# MASTER_GPIO.net
KiCad netlist of a schematic drawn in Altium Designer
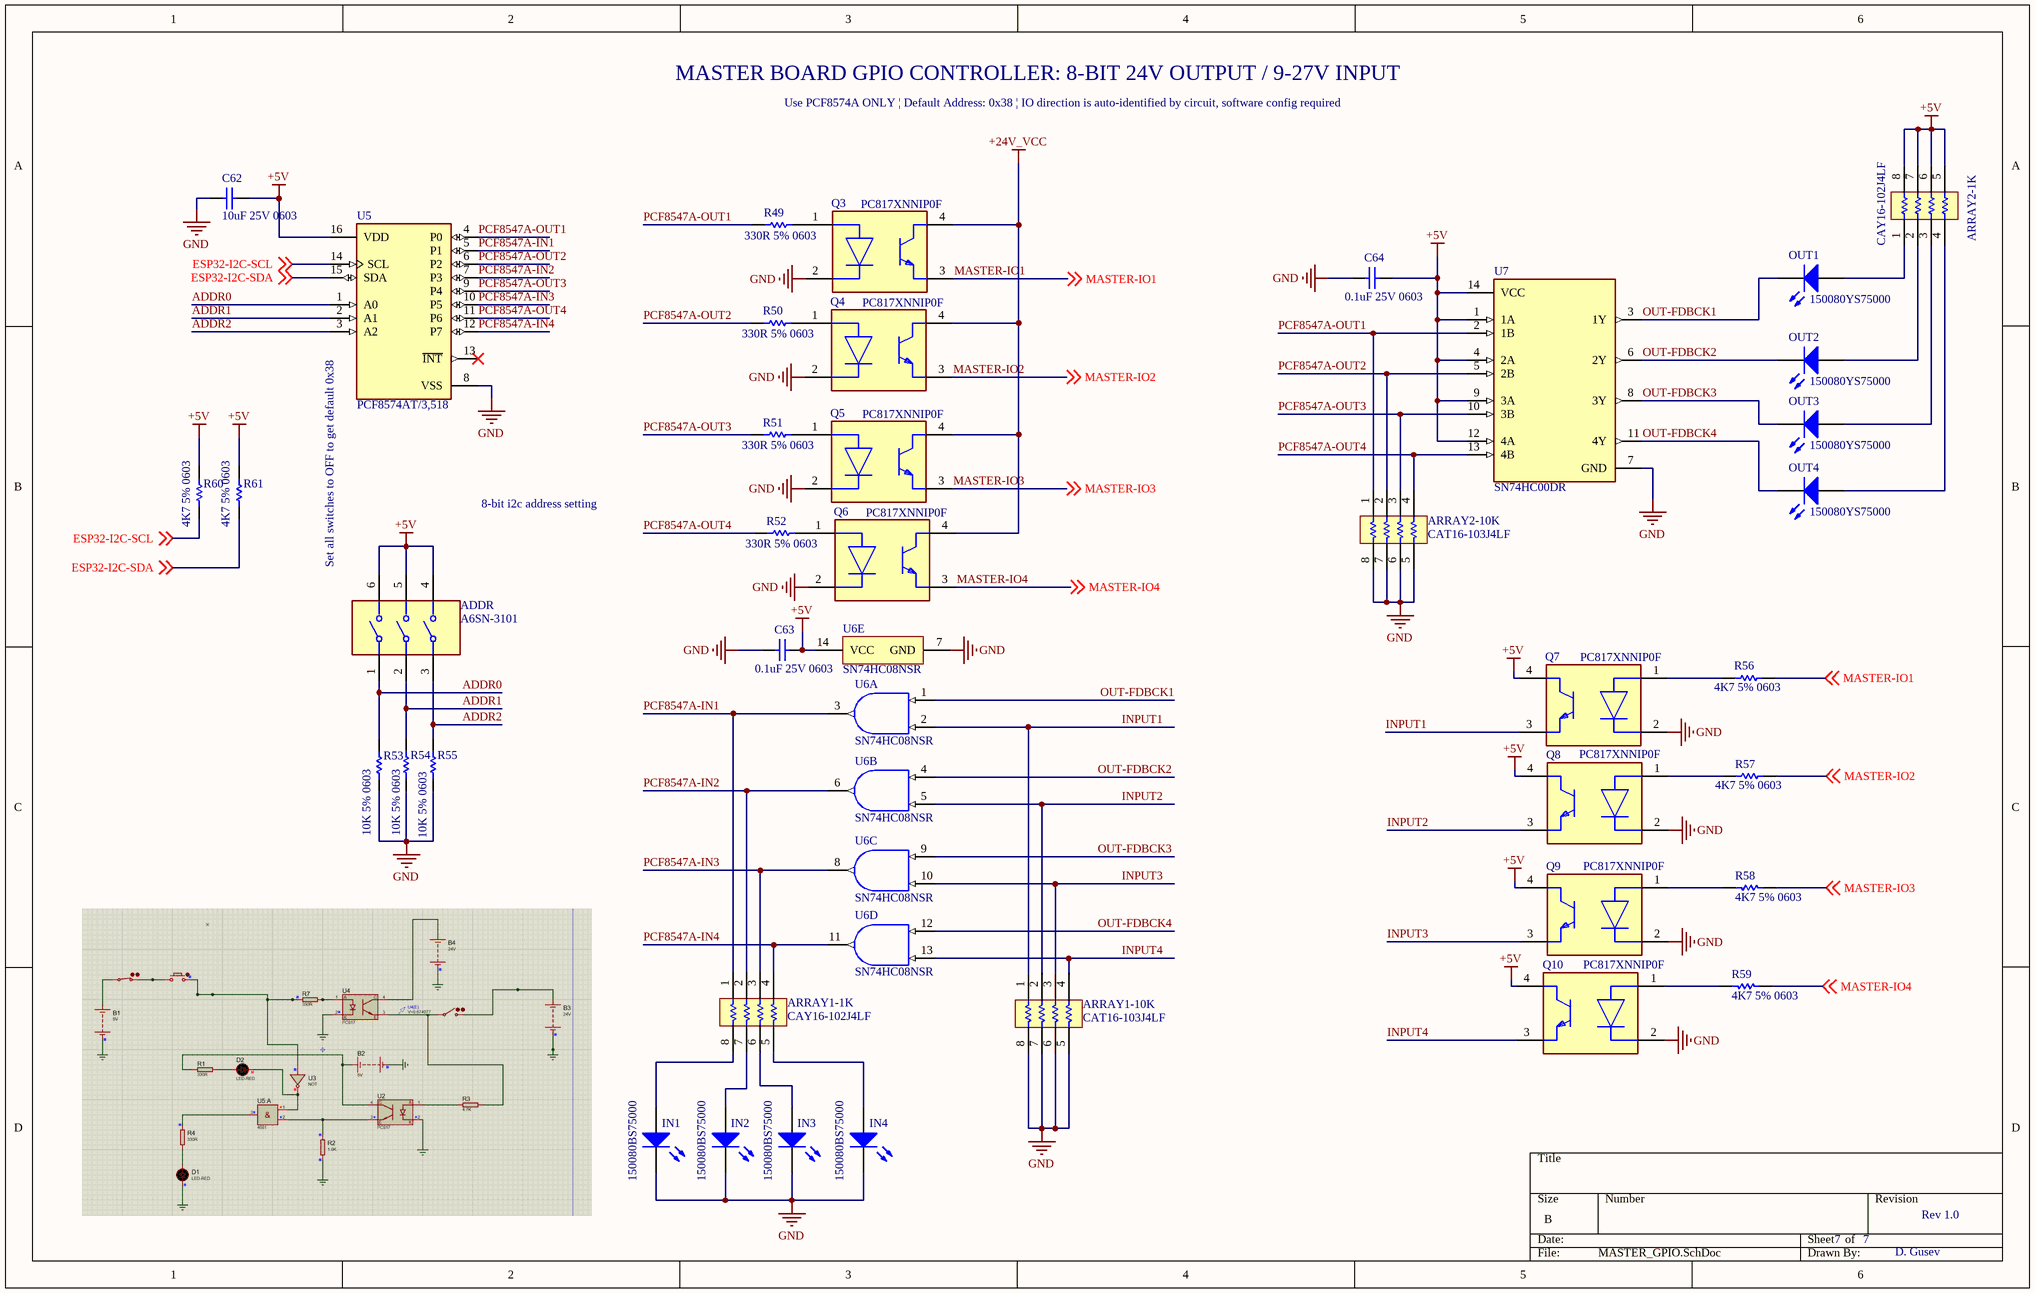
[diagram p0: MASTER_GPIO.SchDoc]

(export (version "E")
  (design (tool "Eeschema 10.0.6"))
  (components
    (comp (ref "ADDR")
      (value "A6SN-3101")
      (footprint "FP-A6SN-3101-MFG")
      (description "SWITCH SLIDE DIP SPST 25MA 24V")
      (fields
        (field (name "MANUFACTURER") "Omron Electronics Inc-EMC Div")
        (field (name "OCTOPART") "https://octopart.com/a6sn-3101-omron-55396000")
      )
      (libsource (lib "Altium Content Vault") (part "c5ed29025a0a80be921a75429a93ff4"))
    )
    (comp (ref "ARRAY1-1K")
      (value "CAY16-102J4LF")
      (footprint "BOUR-CAY16-J4_V")
      (description "Chip Resistor Array, 1 KOhm, +/- 5%, 62.5 mW, -55 to 125 degC, 8-Pin SMD, RoHS, Tape and Reel")
      (fields (field (name "TOLERANCE") "1%"))
      (libsource (lib "Altium Content Vault") (part "RES-P-8"))
    )
    (comp (ref "ARRAY1-10K")
      (value "CAT16-103J4LF")
      (footprint "BOUR-CAT16-103J4LF_L")
      (fields (field (name "MANUFACTURER") "Bourns") (field (name "TOLERANCE") "±5%"))
      (libsource (lib "Altium Content Vault") (part "RES-P-8"))
    )
    (comp (ref "ARRAY2-1K")
      (value "CAY16-102J4LF")
      (footprint "BOUR-CAY16-J4_V")
      (description "Chip Resistor Array, 1 KOhm, +/- 5%, 62.5 mW, -55 to 125 degC, 8-Pin SMD, RoHS, Tape and Reel")
      (fields (field (name "TOLERANCE") "1%"))
      (libsource (lib "") (part "RES-P-8_1"))
    )
    (comp (ref "ARRAY2-10K")
      (value "CAT16-103J4LF")
      (footprint "BOUR-CAT16-103J4LF_L")
      (fields (field (name "MANUFACTURER") "Bourns") (field (name "TOLERANCE") "±5%"))
      (libsource (lib "Altium Content Vault") (part "RES-P-8"))
    )
    (comp (ref "C62")
      (value "10uF 25V 0603")
      (footprint "CAPC1608X100X20VL10T10")
      (description "Chip Capacitor, 10 uF, +/- 20%, 25 V, -55 to 85 degC, 0603 (1608 Metric), RoHS, Tape and Reel")
      (fields (field (name "MANUFACTURER") "TDK") (field (name "TOLERANCE") "±20%"))
      (libsource (lib "Altium Content Vault") (part "CAP-NP-2"))
    )
    (comp (ref "C63")
      (value "0.1uF 25V 0603")
      (footprint "CAPC1608X90X35LL10T15")
      (fields (field (name "PART NUMBER") "GRM188R71E104KA01D") (field (name "MANUFACTURER") "Murata"))
      (libsource (lib "Altium Content Vault") (part "CAP"))
    )
    (comp (ref "C64")
      (value "0.1uF 25V 0603")
      (footprint "CAPC1608X90X35LL10T15")
      (fields (field (name "PART NUMBER") "GRM188R71E104KA01D") (field (name "MANUFACTURER") "Murata"))
      (libsource (lib "Altium Content Vault") (part "CAP"))
    )
    (comp (ref "IN1")
      (value "150080BS75000")
      (footprint "0805_A")
      (description "SMD mono-color Chip LED, WL-SMCW, Blue")
      (fields (field (name "MANUFACTURER") "Wuerth Elektronik"))
      (libsource (lib "Altium Content Vault") (part "WE-LED_K1A2-2"))
    )
    (comp (ref "IN2")
      (value "150080BS75000")
      (footprint "0805_A")
      (description "SMD mono-color Chip LED, WL-SMCW, Blue")
      (fields (field (name "MANUFACTURER") "Wuerth Elektronik"))
      (libsource (lib "Altium Content Vault") (part "WE-LED_K1A2-2"))
    )
    (comp (ref "IN3")
      (value "150080BS75000")
      (footprint "0805_A")
      (description "SMD mono-color Chip LED, WL-SMCW, Blue")
      (fields (field (name "MANUFACTURER") "Wuerth Elektronik"))
      (libsource (lib "Altium Content Vault") (part "WE-LED_K1A2-2"))
    )
    (comp (ref "IN4")
      (value "150080BS75000")
      (footprint "0805_A")
      (description "SMD mono-color Chip LED, WL-SMCW, Blue")
      (fields (field (name "MANUFACTURER") "Wuerth Elektronik"))
      (libsource (lib "Altium Content Vault") (part "WE-LED_K1A2-2"))
    )
    (comp (ref "OUT1")
      (value "150080YS75000")
      (footprint "0805_A")
      (description "SMD mono-color Chip LED, WL-SMCW, Yellow")
      (fields (field (name "MANUFACTURER") "Wuerth Elektronik"))
      (libsource (lib "Altium Content Vault") (part "WE-LED_K1A2-2"))
    )
    (comp (ref "OUT2")
      (value "150080YS75000")
      (footprint "0805_A")
      (description "SMD mono-color Chip LED, WL-SMCW, Yellow")
      (fields (field (name "MANUFACTURER") "Wuerth Elektronik"))
      (libsource (lib "Altium Content Vault") (part "WE-LED_K1A2-2"))
    )
    (comp (ref "OUT3")
      (value "150080YS75000")
      (footprint "0805_A")
      (description "SMD mono-color Chip LED, WL-SMCW, Yellow")
      (fields (field (name "MANUFACTURER") "Wuerth Elektronik"))
      (libsource (lib "Altium Content Vault") (part "WE-LED_K1A2-2"))
    )
    (comp (ref "OUT4")
      (value "150080YS75000")
      (footprint "0805_A")
      (description "SMD mono-color Chip LED, WL-SMCW, Yellow")
      (fields (field (name "MANUFACTURER") "Wuerth Elektronik"))
      (libsource (lib "Altium Content Vault") (part "WE-LED_K1A2-2"))
    )
    (comp (ref "Q3")
      (value "PC817XNNIP0F")
      (footprint "FP-PC817XNNIP0F-MFG")
      (description "OPTOISOLATOR 5KV TRANS 4SMD")
      (libsource (lib "") (part "6470904bf6395c62928ee73e60120b8_1"))
    )
    (comp (ref "Q4")
      (value "PC817XNNIP0F")
      (footprint "FP-PC817XNNIP0F-MFG")
      (description "OPTOISOLATOR 5KV TRANS 4SMD")
      (libsource (lib "") (part "6470904bf6395c62928ee73e60120b8_1"))
    )
    (comp (ref "Q5")
      (value "PC817XNNIP0F")
      (footprint "FP-PC817XNNIP0F-MFG")
      (description "OPTOISOLATOR 5KV TRANS 4SMD")
      (libsource (lib "") (part "6470904bf6395c62928ee73e60120b8_1"))
    )
    (comp (ref "Q6")
      (value "PC817XNNIP0F")
      (footprint "FP-PC817XNNIP0F-MFG")
      (description "OPTOISOLATOR 5KV TRANS 4SMD")
      (libsource (lib "") (part "6470904bf6395c62928ee73e60120b8_1"))
    )
    (comp (ref "Q7")
      (value "PC817XNNIP0F")
      (footprint "FP-PC817XNNIP0F-MFG")
      (description "OPTOISOLATOR 5KV TRANS 4SMD")
      (libsource (lib "Altium Content Vault") (part "6470904bf6395c62928ee73e60120b8"))
    )
    (comp (ref "Q8")
      (value "PC817XNNIP0F")
      (footprint "FP-PC817XNNIP0F-MFG")
      (description "OPTOISOLATOR 5KV TRANS 4SMD")
      (libsource (lib "Altium Content Vault") (part "6470904bf6395c62928ee73e60120b8"))
    )
    (comp (ref "Q9")
      (value "PC817XNNIP0F")
      (footprint "FP-PC817XNNIP0F-MFG")
      (description "OPTOISOLATOR 5KV TRANS 4SMD")
      (libsource (lib "Altium Content Vault") (part "6470904bf6395c62928ee73e60120b8"))
    )
    (comp (ref "Q10")
      (value "PC817XNNIP0F")
      (footprint "FP-PC817XNNIP0F-MFG")
      (description "OPTOISOLATOR 5KV TRANS 4SMD")
      (libsource (lib "Altium Content Vault") (part "6470904bf6395c62928ee73e60120b8"))
    )
    (comp (ref "R49")
      (value "330R 5% 0603")
      (footprint "RESC1608X55X25NL10T15")
      (description "Chip Resistor, 330 Ohm, +/- 1%, 0.1 W, -55 to 155 degC, 0603 (1608 Metric), RoHS, Tape and Reel")
      (fields (field (name "TOLERANCE") "10%"))
      (libsource (lib "Altium Content Vault") (part "RES-2"))
    )
    (comp (ref "R50")
      (value "330R 5% 0603")
      (footprint "RESC1608X55X25NL10T15")
      (description "Chip Resistor, 330 Ohm, +/- 1%, 0.1 W, -55 to 155 degC, 0603 (1608 Metric), RoHS, Tape and Reel")
      (fields (field (name "TOLERANCE") "10%"))
      (libsource (lib "Altium Content Vault") (part "RES-2"))
    )
    (comp (ref "R51")
      (value "330R 5% 0603")
      (footprint "RESC1608X55X25NL10T15")
      (description "Chip Resistor, 330 Ohm, +/- 1%, 0.1 W, -55 to 155 degC, 0603 (1608 Metric), RoHS, Tape and Reel")
      (fields (field (name "TOLERANCE") "10%"))
      (libsource (lib "Altium Content Vault") (part "RES-2"))
    )
    (comp (ref "R52")
      (value "330R 5% 0603")
      (footprint "RESC1608X55X25NL10T15")
      (description "Chip Resistor, 330 Ohm, +/- 1%, 0.1 W, -55 to 155 degC, 0603 (1608 Metric), RoHS, Tape and Reel")
      (fields (field (name "TOLERANCE") "10%"))
      (libsource (lib "Altium Content Vault") (part "RES-2"))
    )
    (comp (ref "R53")
      (value "10K 5% 0603")
      (footprint "RESC1608X55X25ML10T15")
      (description "Chip Resistor, 10 KOhm, +/- 1%, 01 W, -55 to 155 degC, 0603 (1608 Metric), RoHS, Tape and Reel")
      (fields (field (name "MANUFACTURER") "Yageo") (field (name "TOLERANCE") "1%"))
      (libsource (lib "Altium Content Vault") (part "RES-2"))
    )
    (comp (ref "R54")
      (value "10K 5% 0603")
      (footprint "RESC1608X55X25ML10T15")
      (description "Chip Resistor, 10 KOhm, +/- 1%, 01 W, -55 to 155 degC, 0603 (1608 Metric), RoHS, Tape and Reel")
      (fields (field (name "MANUFACTURER") "Yageo") (field (name "TOLERANCE") "1%"))
      (libsource (lib "Altium Content Vault") (part "RES-2"))
    )
    (comp (ref "R55")
      (value "10K 5% 0603")
      (footprint "RESC1608X55X25ML10T15")
      (description "Chip Resistor, 10 KOhm, +/- 1%, 01 W, -55 to 155 degC, 0603 (1608 Metric), RoHS, Tape and Reel")
      (fields (field (name "MANUFACTURER") "Yageo") (field (name "TOLERANCE") "1%"))
      (libsource (lib "Altium Content Vault") (part "RES-2"))
    )
    (comp (ref "R56")
      (value "4K7 5% 0603")
      (footprint "RESC1608X55X25LL10T15")
      (description "Chip Resistor, 4.7 KOhm, +/- 1%, 0.1 W, -55 to 155 degC, 0603 (1608 Metric), RoHS, Tape and Reel")
      (fields (field (name "MANUFACTURER") "Yageo") (field (name "TOLERANCE") "1%"))
      (libsource (lib "Altium Content Vault") (part "RES-2"))
    )
    (comp (ref "R57")
      (value "4K7 5% 0603")
      (footprint "RESC1608X55X25LL10T15")
      (description "Chip Resistor, 4.7 KOhm, +/- 1%, 0.1 W, -55 to 155 degC, 0603 (1608 Metric), RoHS, Tape and Reel")
      (fields (field (name "MANUFACTURER") "Yageo") (field (name "TOLERANCE") "1%"))
      (libsource (lib "Altium Content Vault") (part "RES-2"))
    )
    (comp (ref "R58")
      (value "4K7 5% 0603")
      (footprint "RESC1608X55X25LL10T15")
      (description "Chip Resistor, 4.7 KOhm, +/- 1%, 0.1 W, -55 to 155 degC, 0603 (1608 Metric), RoHS, Tape and Reel")
      (fields (field (name "MANUFACTURER") "Yageo") (field (name "TOLERANCE") "1%"))
      (libsource (lib "Altium Content Vault") (part "RES-2"))
    )
    (comp (ref "R59")
      (value "4K7 5% 0603")
      (footprint "RESC1608X55X25LL10T15")
      (description "Chip Resistor, 4.7 KOhm, +/- 1%, 0.1 W, -55 to 155 degC, 0603 (1608 Metric), RoHS, Tape and Reel")
      (fields (field (name "MANUFACTURER") "Yageo") (field (name "TOLERANCE") "1%"))
      (libsource (lib "Altium Content Vault") (part "RES-2"))
    )
    (comp (ref "R60")
      (value "4K7 5% 0603")
      (footprint "RESC1608X55X25LL10T15")
      (description "Chip Resistor, 4.7 KOhm, +/- 1%, 0.1 W, -55 to 155 degC, 0603 (1608 Metric), RoHS, Tape and Reel")
      (fields (field (name "MANUFACTURER") "Yageo") (field (name "TOLERANCE") "1%"))
      (libsource (lib "Altium Content Vault") (part "RES-2"))
    )
    (comp (ref "R61")
      (value "4K7 5% 0603")
      (footprint "RESC1608X55X25LL10T15")
      (description "Chip Resistor, 4.7 KOhm, +/- 1%, 0.1 W, -55 to 155 degC, 0603 (1608 Metric), RoHS, Tape and Reel")
      (fields (field (name "MANUFACTURER") "Yageo") (field (name "TOLERANCE") "1%"))
      (libsource (lib "Altium Content Vault") (part "RES-2"))
    )
    (comp (ref "U5")
      (value "PCF8574AT/3,518")
      (footprint "FP-SOT162-1-MFG")
      (description "IC I/O EXPANDER I2C 8B 16SOIC")
      (fields
        (field (name "MANUFACTURER") "NXP Semiconductors")
        (field (name "OCTOPART") "https://octopart.com/pcf8574at%2F3%2C518-nxp+semiconductors-11541925")
      )
      (libsource (lib "Altium Content Vault") (part "f7fde53ce59de981fb0b266a4e103eb"))
    )
    (comp (ref "U6")
      (value "SN74HC08NSR")
      (footprint "NS0014A_M")
      (description "Quadruple 2-Input Positive-AND Gates, NS0014A, LARGE T&R")
      (fields
        (field (name "GENERIC PART NUMBER") "SN74HC08")
        (field (name "MANUFACTURER") "Texas Instruments")
      )
      (libsource (lib "") (part "TI-AND-4-2IN-14_1"))
    )
    (comp (ref "U7")
      (value "SN74HC00DR")
      (footprint "FP-D0014A-MFG")
      (description "IC GATE NAND 4CH 2-INP 14SOIC")
      (libsource (lib "Altium Content Vault") (part "2c7ba7b3eb294338d27c07afa77b609"))
    )
  )
  (nets
    (net (code "1") (name "+5V") (class "Default")
      (node (ref "ADDR") (pin "4") (pinfunction "4_4") (pintype "passive"))
      (node (ref "ADDR") (pin "5") (pinfunction "5_5") (pintype "passive"))
      (node (ref "ADDR") (pin "6") (pinfunction "6_6") (pintype "passive"))
      (node (ref "ARRAY2-1K") (pin "5") (pinfunction "5_5") (pintype "passive"))
      (node (ref "ARRAY2-1K") (pin "6") (pinfunction "6_6") (pintype "passive"))
      (node (ref "ARRAY2-1K") (pin "7") (pinfunction "7_7") (pintype "passive"))
      (node (ref "ARRAY2-1K") (pin "8") (pinfunction "8_8") (pintype "passive"))
      (node (ref "C62") (pin "1") (pinfunction "1_1") (pintype "passive"))
      (node (ref "C63") (pin "1") (pinfunction "1_1") (pintype "passive"))
      (node (ref "C64") (pin "1") (pinfunction "1_1") (pintype "passive"))
      (node (ref "Q10") (pin "4") (pinfunction "C_4") (pintype "passive"))
      (node (ref "Q7") (pin "4") (pinfunction "C_4") (pintype "passive"))
      (node (ref "Q8") (pin "4") (pinfunction "C_4") (pintype "passive"))
      (node (ref "Q9") (pin "4") (pinfunction "C_4") (pintype "passive"))
      (node (ref "R60") (pin "2") (pinfunction "2_2") (pintype "passive"))
      (node (ref "R61") (pin "2") (pinfunction "2_2") (pintype "passive"))
      (node (ref "U5") (pin "16") (pinfunction "VDD_16") (pintype "power_in"))
      (node (ref "U6") (pin "14") (pinfunction "VCC_14") (pintype "power_in"))
      (node (ref "U7") (pin "1") (pinfunction "1A_1") (pintype "input"))
      (node (ref "U7") (pin "12") (pinfunction "4A_12") (pintype "input"))
      (node (ref "U7") (pin "14") (pinfunction "VCC_14") (pintype "power_in"))
      (node (ref "U7") (pin "4") (pinfunction "2A_4") (pintype "input"))
      (node (ref "U7") (pin "9") (pinfunction "3A_9") (pintype "input"))
    )
    (net (code "2") (name "+24V_VCC") (class "Default")
      (node (ref "Q3") (pin "4") (pinfunction "C_4") (pintype "passive"))
      (node (ref "Q4") (pin "4") (pinfunction "C_4") (pintype "passive"))
      (node (ref "Q5") (pin "4") (pinfunction "C_4") (pintype "passive"))
      (node (ref "Q6") (pin "4") (pinfunction "C_4") (pintype "passive"))
    )
    (net (code "3") (name "/ADDR0") (class "Default")
      (node (ref "ADDR") (pin "1") (pinfunction "1_1") (pintype "passive"))
      (node (ref "R53") (pin "2") (pinfunction "2_2") (pintype "passive"))
      (node (ref "U5") (pin "1") (pinfunction "A0_1") (pintype "input"))
    )
    (net (code "4") (name "/ADDR1") (class "Default")
      (node (ref "ADDR") (pin "2") (pinfunction "2_2") (pintype "passive"))
      (node (ref "R54") (pin "2") (pinfunction "2_2") (pintype "passive"))
      (node (ref "U5") (pin "2") (pinfunction "A1_2") (pintype "input"))
    )
    (net (code "5") (name "/ADDR2") (class "Default")
      (node (ref "ADDR") (pin "3") (pinfunction "3_3") (pintype "passive"))
      (node (ref "R55") (pin "2") (pinfunction "2_2") (pintype "passive"))
      (node (ref "U5") (pin "3") (pinfunction "A2_3") (pintype "input"))
    )
    (net (code "6") (name "/INPUT1") (class "Default")
      (node (ref "ARRAY1-10K") (pin "1") (pinfunction "1_1") (pintype "passive"))
      (node (ref "Q7") (pin "3") (pinfunction "E_3") (pintype "passive"))
      (node (ref "U6") (pin "2") (pinfunction "1B_2") (pintype "input"))
    )
    (net (code "7") (name "/INPUT2") (class "Default")
      (node (ref "ARRAY1-10K") (pin "2") (pinfunction "2_2") (pintype "passive"))
      (node (ref "Q8") (pin "3") (pinfunction "E_3") (pintype "passive"))
      (node (ref "U6") (pin "5") (pinfunction "2B_5") (pintype "input"))
    )
    (net (code "8") (name "/INPUT3") (class "Default")
      (node (ref "ARRAY1-10K") (pin "3") (pinfunction "3_3") (pintype "passive"))
      (node (ref "Q9") (pin "3") (pinfunction "E_3") (pintype "passive"))
      (node (ref "U6") (pin "10") (pinfunction "3B_10") (pintype "input"))
    )
    (net (code "9") (name "/INPUT4") (class "Default")
      (node (ref "ARRAY1-10K") (pin "4") (pinfunction "4_4") (pintype "passive"))
      (node (ref "Q10") (pin "3") (pinfunction "E_3") (pintype "passive"))
      (node (ref "U6") (pin "13") (pinfunction "4B_13") (pintype "input"))
    )
    (net (code "10") (name "/OUT-FDBCK1") (class "Default")
      (node (ref "OUT1") (pin "1") (pinfunction "K_1") (pintype "passive"))
      (node (ref "U6") (pin "1") (pinfunction "1A_1") (pintype "input"))
      (node (ref "U7") (pin "3") (pinfunction "1Y_3") (pintype "output"))
    )
    (net (code "11") (name "/OUT-FDBCK2") (class "Default")
      (node (ref "OUT2") (pin "1") (pinfunction "K_1") (pintype "passive"))
      (node (ref "U6") (pin "4") (pinfunction "2A_4") (pintype "input"))
      (node (ref "U7") (pin "6") (pinfunction "2Y_6") (pintype "output"))
    )
    (net (code "12") (name "/OUT-FDBCK3") (class "Default")
      (node (ref "OUT3") (pin "1") (pinfunction "K_1") (pintype "passive"))
      (node (ref "U6") (pin "9") (pinfunction "3A_9") (pintype "input"))
      (node (ref "U7") (pin "8") (pinfunction "3Y_8") (pintype "output"))
    )
    (net (code "13") (name "/OUT-FDBCK4") (class "Default")
      (node (ref "OUT4") (pin "1") (pinfunction "K_1") (pintype "passive"))
      (node (ref "U6") (pin "12") (pinfunction "4A_12") (pintype "input"))
      (node (ref "U7") (pin "11") (pinfunction "4Y_11") (pintype "output"))
    )
    (net (code "14") (name "/PCF8547A-IN1") (class "Default")
      (node (ref "ARRAY1-1K") (pin "1") (pinfunction "1_1") (pintype "passive"))
      (node (ref "U5") (pin "5") (pinfunction "P1_5") (pintype "bidirectional"))
      (node (ref "U6") (pin "3") (pinfunction "1Y_3") (pintype "output"))
    )
    (net (code "15") (name "/PCF8547A-IN2") (class "Default")
      (node (ref "ARRAY1-1K") (pin "2") (pinfunction "2_2") (pintype "passive"))
      (node (ref "U5") (pin "7") (pinfunction "P3_7") (pintype "bidirectional"))
      (node (ref "U6") (pin "6") (pinfunction "2Y_6") (pintype "output"))
    )
    (net (code "16") (name "/PCF8547A-IN3") (class "Default")
      (node (ref "ARRAY1-1K") (pin "3") (pinfunction "3_3") (pintype "passive"))
      (node (ref "U5") (pin "10") (pinfunction "P5_10") (pintype "bidirectional"))
      (node (ref "U6") (pin "8") (pinfunction "3Y_8") (pintype "output"))
    )
    (net (code "17") (name "/PCF8547A-IN4") (class "Default")
      (node (ref "ARRAY1-1K") (pin "4") (pinfunction "4_4") (pintype "passive"))
      (node (ref "U5") (pin "12") (pinfunction "P7_12") (pintype "bidirectional"))
      (node (ref "U6") (pin "11") (pinfunction "4Y_11") (pintype "output"))
    )
    (net (code "18") (name "/PCF8547A-OUT1") (class "Default")
      (node (ref "ARRAY2-10K") (pin "1") (pinfunction "1_1") (pintype "passive"))
      (node (ref "R49") (pin "1") (pinfunction "1_1") (pintype "passive"))
      (node (ref "U5") (pin "4") (pinfunction "P0_4") (pintype "bidirectional"))
      (node (ref "U7") (pin "2") (pinfunction "1B_2") (pintype "input"))
    )
    (net (code "19") (name "/PCF8547A-OUT2") (class "Default")
      (node (ref "ARRAY2-10K") (pin "2") (pinfunction "2_2") (pintype "passive"))
      (node (ref "R50") (pin "1") (pinfunction "1_1") (pintype "passive"))
      (node (ref "U5") (pin "6") (pinfunction "P2_6") (pintype "bidirectional"))
      (node (ref "U7") (pin "5") (pinfunction "2B_5") (pintype "input"))
    )
    (net (code "20") (name "/PCF8547A-OUT3") (class "Default")
      (node (ref "ARRAY2-10K") (pin "3") (pinfunction "3_3") (pintype "passive"))
      (node (ref "R51") (pin "1") (pinfunction "1_1") (pintype "passive"))
      (node (ref "U5") (pin "9") (pinfunction "P4_9") (pintype "bidirectional"))
      (node (ref "U7") (pin "10") (pinfunction "3B_10") (pintype "input"))
    )
    (net (code "21") (name "/PCF8547A-OUT4") (class "Default")
      (node (ref "ARRAY2-10K") (pin "4") (pinfunction "4_4") (pintype "passive"))
      (node (ref "R52") (pin "1") (pinfunction "1_1") (pintype "passive"))
      (node (ref "U5") (pin "11") (pinfunction "P6_11") (pintype "bidirectional"))
      (node (ref "U7") (pin "13") (pinfunction "4B_13") (pintype "input"))
    )
    (net (code "22") (name "ESP32-I2C-SCL") (class "Default")
      (node (ref "R60") (pin "1") (pinfunction "1_1") (pintype "passive"))
      (node (ref "U5") (pin "14") (pinfunction "SCL_14") (pintype "input"))
    )
    (net (code "23") (name "ESP32-I2C-SDA") (class "Default")
      (node (ref "R61") (pin "1") (pinfunction "1_1") (pintype "passive"))
      (node (ref "U5") (pin "15") (pinfunction "SDA_15") (pintype "bidirectional"))
    )
    (net (code "24") (name "GND") (class "Default")
      (node (ref "ARRAY1-10K") (pin "5") (pinfunction "5_5") (pintype "passive"))
      (node (ref "ARRAY1-10K") (pin "6") (pinfunction "6_6") (pintype "passive"))
      (node (ref "ARRAY1-10K") (pin "7") (pinfunction "7_7") (pintype "passive"))
      (node (ref "ARRAY1-10K") (pin "8") (pinfunction "8_8") (pintype "passive"))
      (node (ref "ARRAY2-10K") (pin "5") (pinfunction "5_5") (pintype "passive"))
      (node (ref "ARRAY2-10K") (pin "6") (pinfunction "6_6") (pintype "passive"))
      (node (ref "ARRAY2-10K") (pin "7") (pinfunction "7_7") (pintype "passive"))
      (node (ref "ARRAY2-10K") (pin "8") (pinfunction "8_8") (pintype "passive"))
      (node (ref "C62") (pin "2") (pinfunction "2_2") (pintype "passive"))
      (node (ref "C63") (pin "2") (pinfunction "2_2") (pintype "passive"))
      (node (ref "C64") (pin "2") (pinfunction "2_2") (pintype "passive"))
      (node (ref "IN1") (pin "1") (pinfunction "K_1") (pintype "passive"))
      (node (ref "IN2") (pin "1") (pinfunction "K_1") (pintype "passive"))
      (node (ref "IN3") (pin "1") (pinfunction "K_1") (pintype "passive"))
      (node (ref "IN4") (pin "1") (pinfunction "K_1") (pintype "passive"))
      (node (ref "Q10") (pin "2") (pinfunction "C_2") (pintype "passive"))
      (node (ref "Q3") (pin "2") (pinfunction "C_2") (pintype "passive"))
      (node (ref "Q4") (pin "2") (pinfunction "C_2") (pintype "passive"))
      (node (ref "Q5") (pin "2") (pinfunction "C_2") (pintype "passive"))
      (node (ref "Q6") (pin "2") (pinfunction "C_2") (pintype "passive"))
      (node (ref "Q7") (pin "2") (pinfunction "C_2") (pintype "passive"))
      (node (ref "Q8") (pin "2") (pinfunction "C_2") (pintype "passive"))
      (node (ref "Q9") (pin "2") (pinfunction "C_2") (pintype "passive"))
      (node (ref "R53") (pin "1") (pinfunction "1_1") (pintype "passive"))
      (node (ref "R54") (pin "1") (pinfunction "1_1") (pintype "passive"))
      (node (ref "R55") (pin "1") (pinfunction "1_1") (pintype "passive"))
      (node (ref "U5") (pin "8") (pinfunction "VSS_8") (pintype "power_in"))
      (node (ref "U6") (pin "7") (pinfunction "GND_7") (pintype "power_in"))
      (node (ref "U7") (pin "7") (pinfunction "GND_7") (pintype "power_in"))
    )
    (net (code "25") (name "MASTER-IO1") (class "Default")
      (node (ref "Q3") (pin "3") (pinfunction "E_3") (pintype "passive"))
      (node (ref "R56") (pin "2") (pinfunction "2_2") (pintype "passive"))
    )
    (net (code "26") (name "MASTER-IO2") (class "Default")
      (node (ref "Q4") (pin "3") (pinfunction "E_3") (pintype "passive"))
      (node (ref "R57") (pin "2") (pinfunction "2_2") (pintype "passive"))
    )
    (net (code "27") (name "MASTER-IO3") (class "Default")
      (node (ref "Q5") (pin "3") (pinfunction "E_3") (pintype "passive"))
      (node (ref "R58") (pin "1") (pinfunction "1_1") (pintype "passive"))
    )
    (net (code "28") (name "MASTER-IO4") (class "Default")
      (node (ref "Q6") (pin "3") (pinfunction "E_3") (pintype "passive"))
      (node (ref "R59") (pin "1") (pinfunction "1_1") (pintype "passive"))
    )
    (net (code "29") (name "Net-(IN1-A)") (class "Default")
      (node (ref "ARRAY1-1K") (pin "8") (pinfunction "8_8") (pintype "passive"))
      (node (ref "IN1") (pin "2") (pinfunction "A_2") (pintype "passive"))
    )
    (net (code "30") (name "Net-(IN2-A)") (class "Default")
      (node (ref "ARRAY1-1K") (pin "7") (pinfunction "7_7") (pintype "passive"))
      (node (ref "IN2") (pin "2") (pinfunction "A_2") (pintype "passive"))
    )
    (net (code "31") (name "Net-(IN3-A)") (class "Default")
      (node (ref "ARRAY1-1K") (pin "6") (pinfunction "6_6") (pintype "passive"))
      (node (ref "IN3") (pin "2") (pinfunction "A_2") (pintype "passive"))
    )
    (net (code "32") (name "Net-(IN4-A)") (class "Default")
      (node (ref "ARRAY1-1K") (pin "5") (pinfunction "5_5") (pintype "passive"))
      (node (ref "IN4") (pin "2") (pinfunction "A_2") (pintype "passive"))
    )
    (net (code "33") (name "Net-(OUT1-A)") (class "Default")
      (node (ref "ARRAY2-1K") (pin "1") (pinfunction "1_1") (pintype "passive"))
      (node (ref "OUT1") (pin "2") (pinfunction "A_2") (pintype "passive"))
    )
    (net (code "34") (name "Net-(OUT2-A)") (class "Default")
      (node (ref "ARRAY2-1K") (pin "2") (pinfunction "2_2") (pintype "passive"))
      (node (ref "OUT2") (pin "2") (pinfunction "A_2") (pintype "passive"))
    )
    (net (code "35") (name "Net-(OUT3-A)") (class "Default")
      (node (ref "ARRAY2-1K") (pin "3") (pinfunction "3_3") (pintype "passive"))
      (node (ref "OUT3") (pin "2") (pinfunction "A_2") (pintype "passive"))
    )
    (net (code "36") (name "Net-(OUT4-A)") (class "Default")
      (node (ref "ARRAY2-1K") (pin "4") (pinfunction "4_4") (pintype "passive"))
      (node (ref "OUT4") (pin "2") (pinfunction "A_2") (pintype "passive"))
    )
    (net (code "37") (name "Net-(Q3-A)") (class "Default")
      (node (ref "Q3") (pin "1") (pinfunction "A_1") (pintype "passive"))
      (node (ref "R49") (pin "2") (pinfunction "2_2") (pintype "passive"))
    )
    (net (code "38") (name "Net-(Q4-A)") (class "Default")
      (node (ref "Q4") (pin "1") (pinfunction "A_1") (pintype "passive"))
      (node (ref "R50") (pin "2") (pinfunction "2_2") (pintype "passive"))
    )
    (net (code "39") (name "Net-(Q5-A)") (class "Default")
      (node (ref "Q5") (pin "1") (pinfunction "A_1") (pintype "passive"))
      (node (ref "R51") (pin "2") (pinfunction "2_2") (pintype "passive"))
    )
    (net (code "40") (name "Net-(Q6-A)") (class "Default")
      (node (ref "Q6") (pin "1") (pinfunction "A_1") (pintype "passive"))
      (node (ref "R52") (pin "2") (pinfunction "2_2") (pintype "passive"))
    )
    (net (code "41") (name "Net-(Q7-A)") (class "Default")
      (node (ref "Q7") (pin "1") (pinfunction "A_1") (pintype "passive"))
      (node (ref "R56") (pin "1") (pinfunction "1_1") (pintype "passive"))
    )
    (net (code "42") (name "Net-(Q8-A)") (class "Default")
      (node (ref "Q8") (pin "1") (pinfunction "A_1") (pintype "passive"))
      (node (ref "R57") (pin "1") (pinfunction "1_1") (pintype "passive"))
    )
    (net (code "43") (name "Net-(Q9-A)") (class "Default")
      (node (ref "Q9") (pin "1") (pinfunction "A_1") (pintype "passive"))
      (node (ref "R58") (pin "2") (pinfunction "2_2") (pintype "passive"))
    )
    (net (code "44") (name "Net-(Q10-A)") (class "Default")
      (node (ref "Q10") (pin "1") (pinfunction "A_1") (pintype "passive"))
      (node (ref "R59") (pin "2") (pinfunction "2_2") (pintype "passive"))
    )
    (net (code "45") (name "unconnected-(U5-~{INT}-Pad13)") (class "Default")
      (node (ref "U5") (pin "13") (pinfunction "~{INT}_13") (pintype "output+no_connect"))
    )
  )
)
